# TestJig.net
KiCad netlist of a schematic drawn in EAGLE
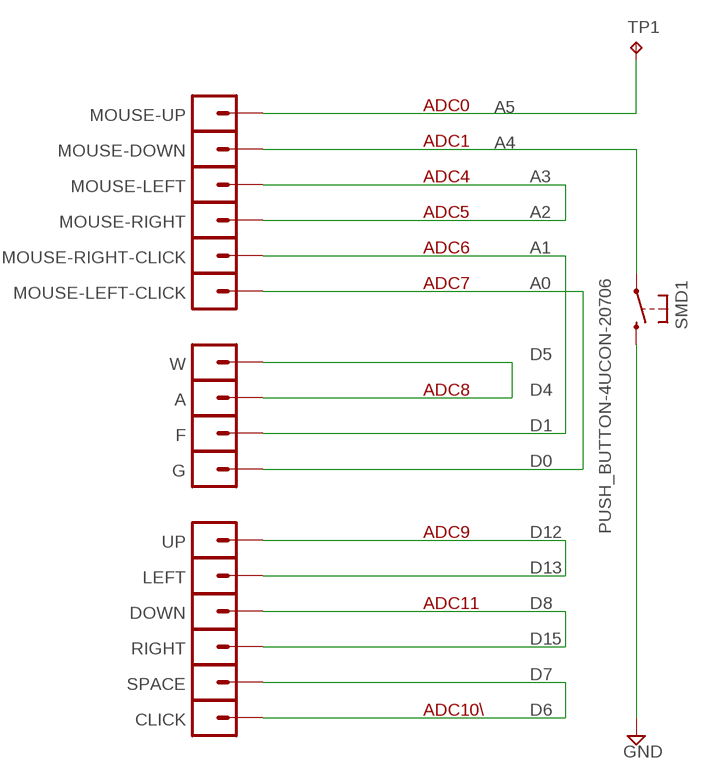
[diagram p0: schematic, sheet 1]

(export (version "E")
  (design (tool "Eeschema 10.0.6"))
  (components
    (comp (ref "A")
      (value "MA01-1-ALLIGATOR-3.0MM")
      (footprint "eagle-import:MA01-1-ALLIGATOR-3.0MM")
      (libsource (lib "eagle-import") (part "MA01-1-ALLIGATOR-3.0MM"))
    )
    (comp (ref "CLICK")
      (value "MA01-1-ALLIGATOR-3.0MM")
      (footprint "eagle-import:MA01-1-ALLIGATOR-3.0MM")
      (libsource (lib "eagle-import") (part "MA01-1-ALLIGATOR-3.0MM"))
    )
    (comp (ref "DOWN")
      (value "MA01-1-ALLIGATOR-3.0MM")
      (footprint "eagle-import:MA01-1-ALLIGATOR-3.0MM")
      (libsource (lib "eagle-import") (part "MA01-1-ALLIGATOR-3.0MM"))
    )
    (comp (ref "F")
      (value "MA01-1-ALLIGATOR-3.0MM")
      (footprint "eagle-import:MA01-1-ALLIGATOR-3.0MM")
      (libsource (lib "eagle-import") (part "MA01-1-ALLIGATOR-3.0MM"))
    )
    (comp (ref "G")
      (value "MA01-1-ALLIGATOR-3.0MM")
      (footprint "eagle-import:MA01-1-ALLIGATOR-3.0MM")
      (libsource (lib "eagle-import") (part "MA01-1-ALLIGATOR-3.0MM"))
    )
    (comp (ref "LEFT")
      (value "MA01-1-ALLIGATOR-3.0MM")
      (footprint "eagle-import:MA01-1-ALLIGATOR-3.0MM")
      (libsource (lib "eagle-import") (part "MA01-1-ALLIGATOR-3.0MM"))
    )
    (comp (ref "MOUSE-DOWN")
      (value "MA01-1-ALLIGATOR-3.0MM")
      (footprint "eagle-import:MA01-1-ALLIGATOR-3.0MM")
      (libsource (lib "eagle-import") (part "MA01-1-ALLIGATOR-3.0MM"))
    )
    (comp (ref "MOUSE-LEFT")
      (value "MA01-1-ALLIGATOR-3.0MM")
      (footprint "eagle-import:MA01-1-ALLIGATOR-3.0MM")
      (libsource (lib "eagle-import") (part "MA01-1-ALLIGATOR-3.0MM"))
    )
    (comp (ref "MOUSE-LEFT-CLICK")
      (value "MA01-1-ALLIGATOR-3.0MM")
      (footprint "eagle-import:MA01-1-ALLIGATOR-3.0MM")
      (libsource (lib "eagle-import") (part "MA01-1-ALLIGATOR-3.0MM"))
    )
    (comp (ref "MOUSE-RIGHT")
      (value "MA01-1-ALLIGATOR-3.0MM")
      (footprint "eagle-import:MA01-1-ALLIGATOR-3.0MM")
      (libsource (lib "eagle-import") (part "MA01-1-ALLIGATOR-3.0MM"))
    )
    (comp (ref "MOUSE-RIGHT-CLICK")
      (value "MA01-1-ALLIGATOR-3.0MM")
      (footprint "eagle-import:MA01-1-ALLIGATOR-3.0MM")
      (libsource (lib "eagle-import") (part "MA01-1-ALLIGATOR-3.0MM"))
    )
    (comp (ref "MOUSE-UP")
      (value "MA01-1-ALLIGATOR-3.0MM")
      (footprint "eagle-import:MA01-1-ALLIGATOR-3.0MM")
      (libsource (lib "eagle-import") (part "MA01-1-ALLIGATOR-3.0MM"))
    )
    (comp (ref "RIGHT")
      (value "MA01-1-ALLIGATOR-3.0MM")
      (footprint "eagle-import:MA01-1-ALLIGATOR-3.0MM")
      (libsource (lib "eagle-import") (part "MA01-1-ALLIGATOR-3.0MM"))
    )
    (comp (ref "SMD1")
      (value "PUSH_BUTTON-4UCON-20706")
      (footprint "eagle-import:PUSH_BUTTON-4UCON-20706")
      (fields (field (name "MF") "4UCON") (field (name "MPN") "20706"))
      (libsource (lib "eagle-import") (part "PUSH_BUTTON-4UCON-20706"))
    )
    (comp (ref "SPACE")
      (value "MA01-1-ALLIGATOR-3.0MM")
      (footprint "eagle-import:MA01-1-ALLIGATOR-3.0MM")
      (libsource (lib "eagle-import") (part "MA01-1-ALLIGATOR-3.0MM"))
    )
    (comp (ref "TP1")
      (value "TESTPAD-2.54MM")
      (footprint "eagle-import:TP-2.54MM")
      (libsource (lib "eagle-import") (part "TESTPAD-2.54MM"))
    )
    (comp (ref "UP")
      (value "MA01-1-ALLIGATOR-3.0MM")
      (footprint "eagle-import:MA01-1-ALLIGATOR-3.0MM")
      (libsource (lib "eagle-import") (part "MA01-1-ALLIGATOR-3.0MM"))
    )
    (comp (ref "W")
      (value "MA01-1-ALLIGATOR-3.0MM")
      (footprint "eagle-import:MA01-1-ALLIGATOR-3.0MM")
      (libsource (lib "eagle-import") (part "MA01-1-ALLIGATOR-3.0MM"))
    )
  )
  (nets
    (net (code "1") (name "/A4") (class "Default")
      (node (ref "MOUSE-DOWN") (pin "1@0") (pinfunction "1_1@0") (pintype "passive"))
      (node (ref "MOUSE-DOWN") (pin "1@1") (pinfunction "1_1@1") (pintype "passive"))
      (node (ref "SMD1") (pin "1") (pinfunction "1_1") (pintype "passive"))
      (node (ref "SMD1") (pin "2") (pinfunction "1_2") (pintype "passive"))
    )
    (net (code "2") (name "/A5") (class "Default")
      (node (ref "MOUSE-UP") (pin "1@0") (pinfunction "1_1@0") (pintype "passive"))
      (node (ref "MOUSE-UP") (pin "1@1") (pinfunction "1_1@1") (pintype "passive"))
      (node (ref "TP1") (pin "TP") (pinfunction "TP_TP") (pintype "input"))
    )
    (net (code "3") (name "GND") (class "Default")
      (node (ref "SMD1") (pin "3") (pinfunction "2_3") (pintype "passive"))
      (node (ref "SMD1") (pin "4") (pinfunction "2_4") (pintype "passive"))
    )
    (net (code "4") (name "Net-(A-1-Pad1@0)") (class "Default")
      (node (ref "A") (pin "1@0") (pinfunction "1_1@0") (pintype "passive"))
      (node (ref "A") (pin "1@1") (pinfunction "1_1@1") (pintype "passive"))
      (node (ref "W") (pin "1@0") (pinfunction "1_1@0") (pintype "passive"))
      (node (ref "W") (pin "1@1") (pinfunction "1_1@1") (pintype "passive"))
    )
    (net (code "5") (name "Net-(CLICK-1-Pad1@0)") (class "Default")
      (node (ref "CLICK") (pin "1@0") (pinfunction "1_1@0") (pintype "passive"))
      (node (ref "CLICK") (pin "1@1") (pinfunction "1_1@1") (pintype "passive"))
      (node (ref "SPACE") (pin "1@0") (pinfunction "1_1@0") (pintype "passive"))
      (node (ref "SPACE") (pin "1@1") (pinfunction "1_1@1") (pintype "passive"))
    )
    (net (code "6") (name "Net-(DOWN-1-Pad1@0)") (class "Default")
      (node (ref "DOWN") (pin "1@0") (pinfunction "1_1@0") (pintype "passive"))
      (node (ref "DOWN") (pin "1@1") (pinfunction "1_1@1") (pintype "passive"))
      (node (ref "RIGHT") (pin "1@0") (pinfunction "1_1@0") (pintype "passive"))
      (node (ref "RIGHT") (pin "1@1") (pinfunction "1_1@1") (pintype "passive"))
    )
    (net (code "7") (name "Net-(F-1-Pad1@0)") (class "Default")
      (node (ref "F") (pin "1@0") (pinfunction "1_1@0") (pintype "passive"))
      (node (ref "F") (pin "1@1") (pinfunction "1_1@1") (pintype "passive"))
      (node (ref "MOUSE-RIGHT-CLICK") (pin "1@0") (pinfunction "1_1@0") (pintype "passive"))
      (node (ref "MOUSE-RIGHT-CLICK") (pin "1@1") (pinfunction "1_1@1") (pintype "passive"))
    )
    (net (code "8") (name "Net-(G-1-Pad1@0)") (class "Default")
      (node (ref "G") (pin "1@0") (pinfunction "1_1@0") (pintype "passive"))
      (node (ref "G") (pin "1@1") (pinfunction "1_1@1") (pintype "passive"))
      (node (ref "MOUSE-LEFT-CLICK") (pin "1@0") (pinfunction "1_1@0") (pintype "passive"))
      (node (ref "MOUSE-LEFT-CLICK") (pin "1@1") (pinfunction "1_1@1") (pintype "passive"))
    )
    (net (code "9") (name "Net-(LEFT-1-Pad1@0)") (class "Default")
      (node (ref "LEFT") (pin "1@0") (pinfunction "1_1@0") (pintype "passive"))
      (node (ref "LEFT") (pin "1@1") (pinfunction "1_1@1") (pintype "passive"))
      (node (ref "UP") (pin "1@0") (pinfunction "1_1@0") (pintype "passive"))
      (node (ref "UP") (pin "1@1") (pinfunction "1_1@1") (pintype "passive"))
    )
    (net (code "10") (name "Net-(MOUSE-LEFT-1-Pad1@0)") (class "Default")
      (node (ref "MOUSE-LEFT") (pin "1@0") (pinfunction "1_1@0") (pintype "passive"))
      (node (ref "MOUSE-LEFT") (pin "1@1") (pinfunction "1_1@1") (pintype "passive"))
      (node (ref "MOUSE-RIGHT") (pin "1@0") (pinfunction "1_1@0") (pintype "passive"))
      (node (ref "MOUSE-RIGHT") (pin "1@1") (pinfunction "1_1@1") (pintype "passive"))
    )
  )
)
